# BTS7960-Breakout-Board.net
KiCad netlist of a schematic drawn in EasyEDA
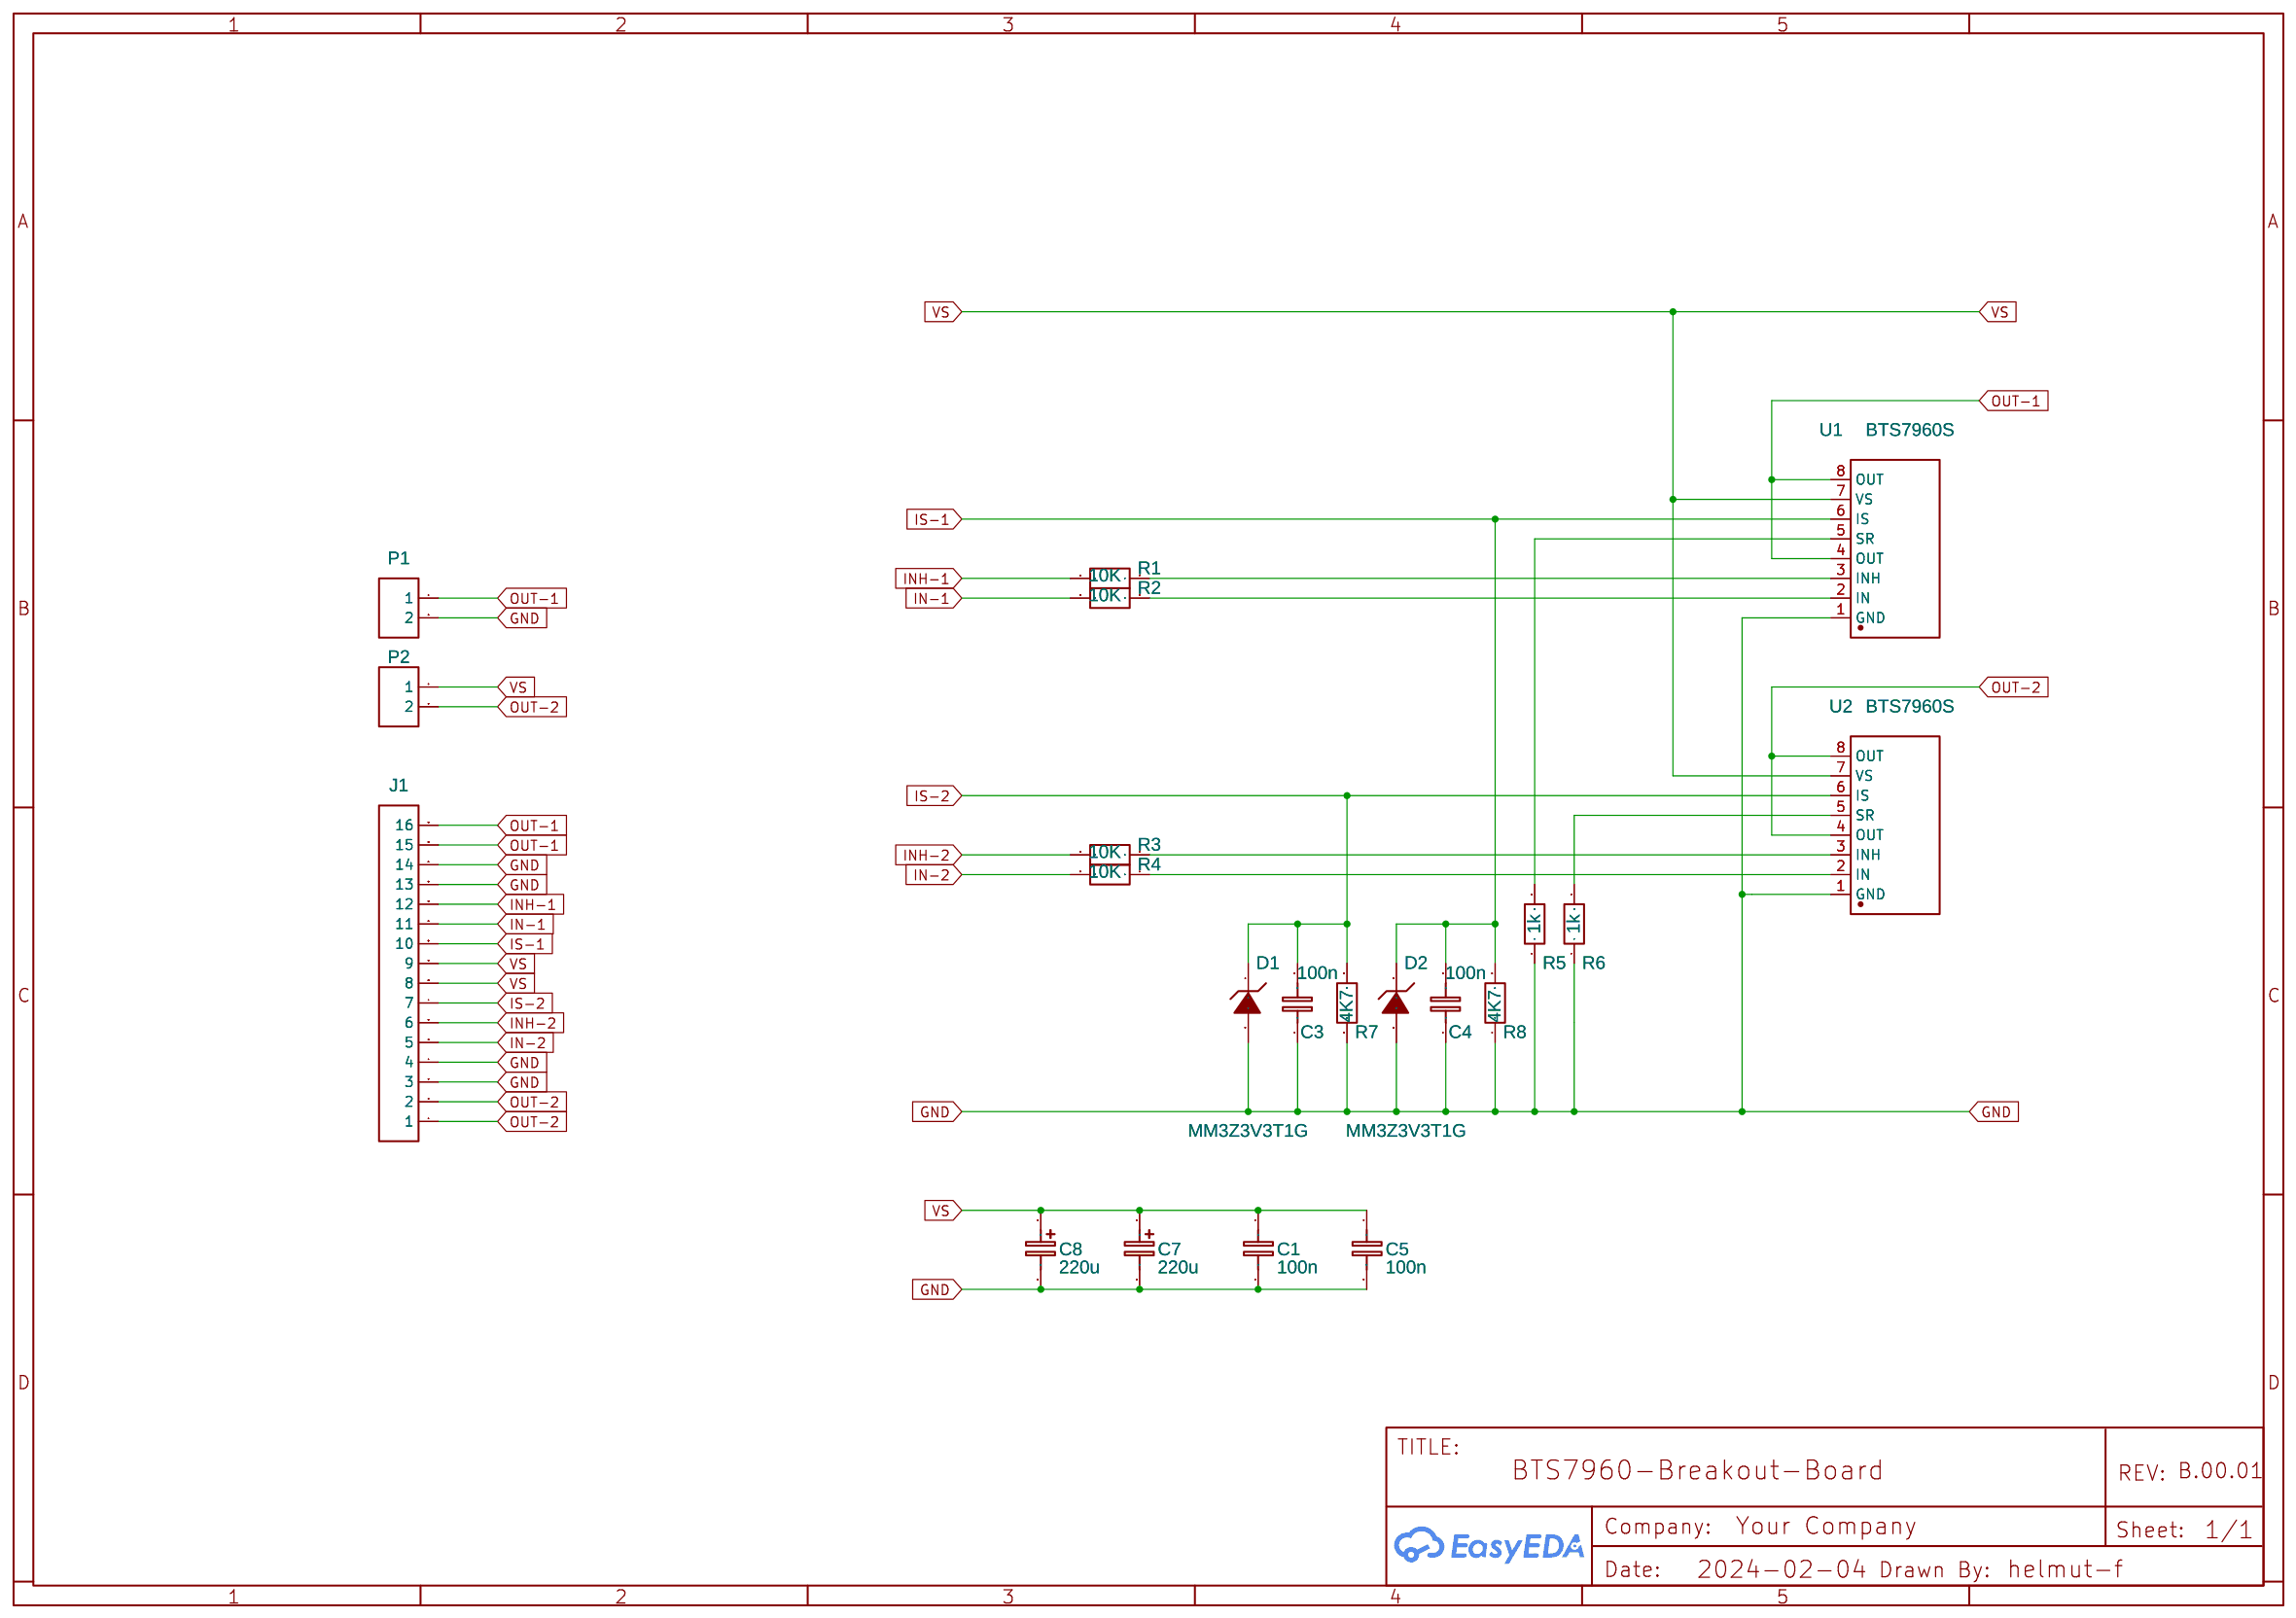
[diagram p0: schematic sheet]

(export (version "E")
  (design (tool "Eeschema 10.0.6"))
  (components
    (comp (ref "C1") (value "100n") (libsource (lib "") (part "C_0603_EU_1")))
    (comp (ref "C3") (value "100n") (libsource (lib "") (part "C_0603_EU")))
    (comp (ref "C4") (value "100n") (libsource (lib "") (part "C_0603_EU")))
    (comp (ref "C5") (value "100n") (libsource (lib "") (part "C_0603_EU_1")))
    (comp (ref "C7") (value "220u") (libsource (lib "") (part "CE_SMD_D5.0×H5.5_EU")))
    (comp (ref "C8") (value "220u") (libsource (lib "") (part "CE_SMD_D5.0×H5.5_EU")))
    (comp (ref "D1")
      (value "MM3Z3V3T1G")
      (fields (field (name "Manufacturer") "onsemi(安森美)"))
      (libsource (lib "") (part "MM3Z3V3T1G"))
    )
    (comp (ref "D2")
      (value "MM3Z3V3T1G")
      (fields (field (name "Manufacturer") "onsemi(安森美)"))
      (libsource (lib "") (part "MM3Z3V3T1G"))
    )
    (comp (ref "J1") (value "HDR-M-2.54_1x16") (libsource (lib "") (part "HDR-M-2.54_1x16")))
    (comp (ref "P1") (value "CONN-TH_2P-P5.08") (libsource (lib "") (part "CONN-TH_2P-P5.08")))
    (comp (ref "P2") (value "CONN-TH_2P-P5.08") (libsource (lib "") (part "CONN-TH_2P-P5.08")))
    (comp (ref "R1") (value "10K") (libsource (lib "") (part "R_AXIAL-0.3_EU_1")))
    (comp (ref "R2") (value "10K") (libsource (lib "") (part "R_AXIAL-0.3_EU_1")))
    (comp (ref "R3") (value "10K") (libsource (lib "") (part "R_AXIAL-0.3_EU_1")))
    (comp (ref "R4") (value "10K") (libsource (lib "") (part "R_AXIAL-0.3_EU_1")))
    (comp (ref "R5") (value "1k") (libsource (lib "") (part "R_AXIAL-0.3_EU")))
    (comp (ref "R6") (value "1k") (libsource (lib "") (part "R_AXIAL-0.3_EU")))
    (comp (ref "R7") (value "4K7") (libsource (lib "") (part "R_AXIAL-0.3_EU")))
    (comp (ref "R8") (value "4K7") (libsource (lib "") (part "R_AXIAL-0.3_EU")))
    (comp (ref "U1")
      (value "BTS7960S")
      (fields (field (name "Manufacturer Part") "bts7960S"))
      (libsource (lib "") (part "BTS7960S"))
    )
    (comp (ref "U2")
      (value "BTS7960S")
      (fields (field (name "Manufacturer Part") "bts7960S"))
      (libsource (lib "") (part "BTS7960S"))
    )
  )
  (nets
    (net (code "1") (name "GND") (class "Default")
      (node (ref "C1") (pin "2") (pinfunction "2_2") (pintype "unspecified"))
      (node (ref "C3") (pin "1") (pinfunction "1_1") (pintype "unspecified"))
      (node (ref "C4") (pin "1") (pinfunction "1_1") (pintype "unspecified"))
      (node (ref "C5") (pin "2") (pinfunction "2_2") (pintype "unspecified"))
      (node (ref "C7") (pin "2") (pinfunction "2_2") (pintype "unspecified"))
      (node (ref "C8") (pin "2") (pinfunction "2_2") (pintype "unspecified"))
      (node (ref "D1") (pin "2") (pinfunction "A_2") (pintype "unspecified"))
      (node (ref "D2") (pin "2") (pinfunction "A_2") (pintype "unspecified"))
      (node (ref "J1") (pin "13") (pinfunction "13_13") (pintype "unspecified"))
      (node (ref "J1") (pin "14") (pinfunction "14_14") (pintype "unspecified"))
      (node (ref "J1") (pin "3") (pinfunction "3_3") (pintype "unspecified"))
      (node (ref "J1") (pin "4") (pinfunction "4_4") (pintype "unspecified"))
      (node (ref "P1") (pin "2") (pinfunction "2_2") (pintype "unspecified"))
      (node (ref "R5") (pin "1") (pinfunction "1_1") (pintype "unspecified"))
      (node (ref "R6") (pin "1") (pinfunction "1_1") (pintype "unspecified"))
      (node (ref "R7") (pin "1") (pinfunction "1_1") (pintype "unspecified"))
      (node (ref "R8") (pin "1") (pinfunction "1_1") (pintype "unspecified"))
      (node (ref "U1") (pin "1") (pinfunction "GND_1") (pintype "unspecified"))
      (node (ref "U2") (pin "1") (pinfunction "GND_1") (pintype "unspecified"))
    )
    (net (code "2") (name "IN-1") (class "Default")
      (node (ref "J1") (pin "11") (pinfunction "11_11") (pintype "unspecified"))
      (node (ref "R2") (pin "2") (pinfunction "2_2") (pintype "unspecified"))
    )
    (net (code "3") (name "IN-2") (class "Default")
      (node (ref "J1") (pin "5") (pinfunction "5_5") (pintype "unspecified"))
      (node (ref "R4") (pin "2") (pinfunction "2_2") (pintype "unspecified"))
    )
    (net (code "4") (name "INH-1") (class "Default")
      (node (ref "J1") (pin "12") (pinfunction "12_12") (pintype "unspecified"))
      (node (ref "R1") (pin "2") (pinfunction "2_2") (pintype "unspecified"))
    )
    (net (code "5") (name "INH-2") (class "Default")
      (node (ref "J1") (pin "6") (pinfunction "6_6") (pintype "unspecified"))
      (node (ref "R3") (pin "2") (pinfunction "2_2") (pintype "unspecified"))
    )
    (net (code "6") (name "IS-1") (class "Default")
      (node (ref "C4") (pin "2") (pinfunction "2_2") (pintype "unspecified"))
      (node (ref "D2") (pin "1") (pinfunction "K_1") (pintype "unspecified"))
      (node (ref "J1") (pin "10") (pinfunction "10_10") (pintype "unspecified"))
      (node (ref "R8") (pin "2") (pinfunction "2_2") (pintype "unspecified"))
      (node (ref "U1") (pin "6") (pinfunction "IS_6") (pintype "unspecified"))
    )
    (net (code "7") (name "IS-2") (class "Default")
      (node (ref "C3") (pin "2") (pinfunction "2_2") (pintype "unspecified"))
      (node (ref "D1") (pin "1") (pinfunction "K_1") (pintype "unspecified"))
      (node (ref "J1") (pin "7") (pinfunction "7_7") (pintype "unspecified"))
      (node (ref "R7") (pin "2") (pinfunction "2_2") (pintype "unspecified"))
      (node (ref "U2") (pin "6") (pinfunction "IS_6") (pintype "unspecified"))
    )
    (net (code "8") (name "Net-(U1-IN)") (class "Default")
      (node (ref "R2") (pin "1") (pinfunction "1_1") (pintype "unspecified"))
      (node (ref "U1") (pin "2") (pinfunction "IN_2") (pintype "unspecified"))
    )
    (net (code "9") (name "Net-(U1-INH)") (class "Default")
      (node (ref "R1") (pin "1") (pinfunction "1_1") (pintype "unspecified"))
      (node (ref "U1") (pin "3") (pinfunction "INH_3") (pintype "unspecified"))
    )
    (net (code "10") (name "Net-(U1-SR)") (class "Default")
      (node (ref "R5") (pin "2") (pinfunction "2_2") (pintype "unspecified"))
      (node (ref "U1") (pin "5") (pinfunction "SR_5") (pintype "unspecified"))
    )
    (net (code "11") (name "Net-(U2-IN)") (class "Default")
      (node (ref "R4") (pin "1") (pinfunction "1_1") (pintype "unspecified"))
      (node (ref "U2") (pin "2") (pinfunction "IN_2") (pintype "unspecified"))
    )
    (net (code "12") (name "Net-(U2-INH)") (class "Default")
      (node (ref "R3") (pin "1") (pinfunction "1_1") (pintype "unspecified"))
      (node (ref "U2") (pin "3") (pinfunction "INH_3") (pintype "unspecified"))
    )
    (net (code "13") (name "Net-(U2-SR)") (class "Default")
      (node (ref "R6") (pin "2") (pinfunction "2_2") (pintype "unspecified"))
      (node (ref "U2") (pin "5") (pinfunction "SR_5") (pintype "unspecified"))
    )
    (net (code "14") (name "OUT-1") (class "Default")
      (node (ref "J1") (pin "15") (pinfunction "15_15") (pintype "unspecified"))
      (node (ref "J1") (pin "16") (pinfunction "16_16") (pintype "unspecified"))
      (node (ref "P1") (pin "1") (pinfunction "1_1") (pintype "unspecified"))
      (node (ref "U1") (pin "4") (pinfunction "OUT_4") (pintype "unspecified"))
      (node (ref "U1") (pin "8") (pinfunction "OUT_8") (pintype "unspecified"))
    )
    (net (code "15") (name "OUT-2") (class "Default")
      (node (ref "J1") (pin "1") (pinfunction "1_1") (pintype "unspecified"))
      (node (ref "J1") (pin "2") (pinfunction "2_2") (pintype "unspecified"))
      (node (ref "P2") (pin "2") (pinfunction "2_2") (pintype "unspecified"))
      (node (ref "U2") (pin "4") (pinfunction "OUT_4") (pintype "unspecified"))
      (node (ref "U2") (pin "8") (pinfunction "OUT_8") (pintype "unspecified"))
    )
    (net (code "16") (name "VS") (class "Default")
      (node (ref "C1") (pin "1") (pinfunction "1_1") (pintype "unspecified"))
      (node (ref "C5") (pin "1") (pinfunction "1_1") (pintype "unspecified"))
      (node (ref "C7") (pin "1") (pinfunction "1_1") (pintype "unspecified"))
      (node (ref "C8") (pin "1") (pinfunction "1_1") (pintype "unspecified"))
      (node (ref "J1") (pin "8") (pinfunction "8_8") (pintype "unspecified"))
      (node (ref "J1") (pin "9") (pinfunction "9_9") (pintype "unspecified"))
      (node (ref "P2") (pin "1") (pinfunction "1_1") (pintype "unspecified"))
      (node (ref "U1") (pin "7") (pinfunction "VS_7") (pintype "unspecified"))
      (node (ref "U2") (pin "7") (pinfunction "VS_7") (pintype "unspecified"))
    )
  )
)
